# Lesson_05_2.net
KiCad netlist of a schematic drawn in Altium Designer
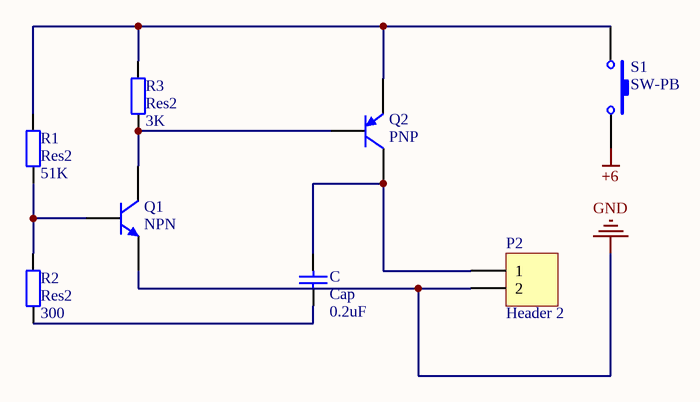
[diagram p0: Lesson_05_2.SchDoc]

(export (version "E")
  (design (tool "Eeschema 10.0.6"))
  (components
    (comp (ref "C")
      (value "Cap")
      (footprint "RAD-0.3")
      (description "Capacitor")
      (fields (field (name "ALTIUM_VALUE") "0.2uF") (field (name "PUBLISHER") "Altium Limited"))
      (libsource (lib "Miscellaneous Devices") (part "Cap"))
    )
    (comp (ref "P2")
      (value "Header 2")
      (footprint "HDR1X2")
      (description "Header, 2-Pin")
      (fields (field (name "PUBLISHER") "Altium Limited"))
      (libsource (lib "Miscellaneous Connectors") (part "Header 2"))
    )
    (comp (ref "Q1")
      (value "NPN")
      (footprint "TO-226-AA")
      (description "NPN Bipolar Transistor")
      (fields (field (name "PUBLISHER") "Altium Limited"))
      (libsource (lib "Miscellaneous Devices") (part "NPN"))
    )
    (comp (ref "Q2")
      (value "PNP")
      (footprint "SOT-23B_N")
      (description "PNP Bipolar Transistor")
      (fields (field (name "PUBLISHER") "Altium Limited"))
      (libsource (lib "Miscellaneous Devices") (part "PNP"))
    )
    (comp (ref "R1")
      (value "Res2")
      (footprint "AXIAL-0.4")
      (description "Resistor")
      (fields (field (name "ALTIUM_VALUE") "51K") (field (name "PUBLISHER") "Altium Limited"))
      (libsource (lib "Miscellaneous Devices") (part "Res2"))
    )
    (comp (ref "R2")
      (value "Res2")
      (footprint "AXIAL-0.4")
      (description "Resistor")
      (fields (field (name "ALTIUM_VALUE") "300") (field (name "PUBLISHER") "Altium Limited"))
      (libsource (lib "Miscellaneous Devices") (part "Res2"))
    )
    (comp (ref "R3")
      (value "Res2")
      (footprint "AXIAL-0.4")
      (description "Resistor")
      (fields (field (name "ALTIUM_VALUE") "3K") (field (name "PUBLISHER") "Altium Limited"))
      (libsource (lib "Miscellaneous Devices") (part "Res2"))
    )
    (comp (ref "S1")
      (value "SW-PB")
      (footprint "SPST-2")
      (description "Switch")
      (fields (field (name "PUBLISHER") "Altium Limited"))
      (libsource (lib "Miscellaneous Devices") (part "SW-PB"))
    )
  )
  (nets
    (net (code "1") (name "+6") (class "Default")
      (node (ref "S1") (pin "2") (pinfunction "2_2") (pintype "passive"))
    )
    (net (code "2") (name "GND") (class "Default")
      (node (ref "P2") (pin "2") (pinfunction "2_2") (pintype "passive"))
      (node (ref "Q1") (pin "3") (pinfunction "E_3") (pintype "passive"))
    )
    (net (code "3") (name "Net-(C-Pad1)") (class "Default")
      (node (ref "C") (pin "1") (pinfunction "1_1") (pintype "passive"))
      (node (ref "R2") (pin "1") (pinfunction "1_1") (pintype "passive"))
    )
    (net (code "4") (name "Net-(Q1-B)") (class "Default")
      (node (ref "Q1") (pin "2") (pinfunction "B_2") (pintype "passive"))
      (node (ref "R1") (pin "1") (pinfunction "1_1") (pintype "passive"))
      (node (ref "R2") (pin "2") (pinfunction "2_2") (pintype "passive"))
    )
    (net (code "5") (name "Net-(Q1-C)") (class "Default")
      (node (ref "Q1") (pin "1") (pinfunction "C_1") (pintype "passive"))
      (node (ref "Q2") (pin "2") (pinfunction "B_2") (pintype "passive"))
      (node (ref "R3") (pin "1") (pinfunction "1_1") (pintype "passive"))
    )
    (net (code "6") (name "Net-(Q2-C)") (class "Default")
      (node (ref "C") (pin "2") (pinfunction "2_2") (pintype "passive"))
      (node (ref "P2") (pin "1") (pinfunction "1_1") (pintype "passive"))
      (node (ref "Q2") (pin "1") (pinfunction "C_1") (pintype "passive"))
    )
    (net (code "7") (name "Net-(Q2-E)") (class "Default")
      (node (ref "Q2") (pin "3") (pinfunction "E_3") (pintype "passive"))
      (node (ref "R1") (pin "2") (pinfunction "2_2") (pintype "passive"))
      (node (ref "R3") (pin "2") (pinfunction "2_2") (pintype "passive"))
      (node (ref "S1") (pin "1") (pinfunction "1_1") (pintype "passive"))
    )
  )
)
